# Safety_2019_V_3_0_Enable.net
KiCad netlist of a schematic drawn in Altium Designer
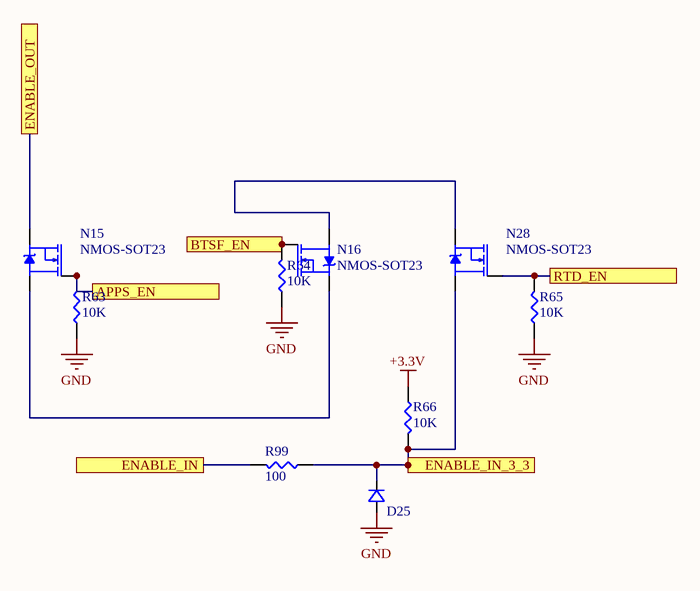
[diagram p0: Safety_2019_V_3_0_Enable.SchDoc]

(export (version "E")
  (design (tool "Eeschema 10.0.6"))
  (components
    (comp (ref "D25")
      (value "12V ZENER")
      (footprint "SOD123")
      (libsource (lib "ife19_Elec_Library") (part "DIODE-SOD123"))
    )
    (comp (ref "N15")
      (value "NMOS-SOT23")
      (footprint "SOT23")
      (libsource (lib "ife19_Elec_Library") (part "NMOS-SOT23"))
    )
    (comp (ref "N16")
      (value "NMOS-SOT23")
      (footprint "SOT23")
      (libsource (lib "ife19_Elec_Library") (part "NMOS-SOT23"))
    )
    (comp (ref "N28")
      (value "NMOS-SOT23")
      (footprint "SOT23")
      (libsource (lib "ife19_Elec_Library") (part "NMOS-SOT23"))
    )
    (comp (ref "R63")
      (value "10K")
      (footprint "RES-0603")
      (libsource (lib "ife19_Elec_Library") (part "RES-0603"))
    )
    (comp (ref "R64")
      (value "10K")
      (footprint "RES-0603")
      (libsource (lib "ife19_Elec_Library") (part "RES-0603"))
    )
    (comp (ref "R65")
      (value "10K")
      (footprint "RES-0603")
      (libsource (lib "ife19_Elec_Library") (part "RES-0603"))
    )
    (comp (ref "R66")
      (value "10K")
      (footprint "RES-0603")
      (libsource (lib "ife19_Elec_Library") (part "RES-0603"))
    )
    (comp (ref "R99")
      (value "100")
      (footprint "RES-0603")
      (libsource (lib "ife19_Elec_Library") (part "RES-0603"))
    )
  )
  (nets
    (net (code "1") (name "+3.3V") (class "Default")
      (node (ref "R66") (pin "1") (pinfunction "1_1") (pintype "passive"))
    )
    (net (code "2") (name "/APPS_EN") (class "Default")
      (node (ref "N15") (pin "1") (pinfunction "G_1") (pintype "passive"))
      (node (ref "R63") (pin "2") (pinfunction "2_2") (pintype "passive"))
    )
    (net (code "3") (name "/BTSF_EN") (class "Default")
      (node (ref "N16") (pin "1") (pinfunction "G_1") (pintype "passive"))
      (node (ref "R64") (pin "2") (pinfunction "2_2") (pintype "passive"))
    )
    (net (code "4") (name "/ENABLE_IN") (class "Default")
      (node (ref "R99") (pin "2") (pinfunction "2_2") (pintype "passive"))
    )
    (net (code "5") (name "/ENABLE_IN_3_3") (class "Default")
      (node (ref "D25") (pin "K") (pinfunction "K_K") (pintype "passive"))
      (node (ref "N28") (pin "2") (pinfunction "S_2") (pintype "passive"))
      (node (ref "R66") (pin "2") (pinfunction "2_2") (pintype "passive"))
      (node (ref "R99") (pin "1") (pinfunction "1_1") (pintype "passive"))
    )
    (net (code "6") (name "/ENABLE_OUT") (class "Default")
      (node (ref "N15") (pin "3") (pinfunction "D_3") (pintype "passive"))
    )
    (net (code "7") (name "/RTD_EN") (class "Default")
      (node (ref "N28") (pin "1") (pinfunction "G_1") (pintype "passive"))
      (node (ref "R65") (pin "2") (pinfunction "2_2") (pintype "passive"))
    )
    (net (code "8") (name "GND") (class "Default")
      (node (ref "D25") (pin "A") (pinfunction "A_A") (pintype "passive"))
      (node (ref "R63") (pin "1") (pinfunction "1_1") (pintype "passive"))
      (node (ref "R64") (pin "1") (pinfunction "1_1") (pintype "passive"))
      (node (ref "R65") (pin "1") (pinfunction "1_1") (pintype "passive"))
    )
    (net (code "9") (name "Net-(N15-S)") (class "Default")
      (node (ref "N15") (pin "2") (pinfunction "S_2") (pintype "passive"))
      (node (ref "N16") (pin "3") (pinfunction "D_3") (pintype "passive"))
    )
    (net (code "10") (name "Net-(N16-S)") (class "Default")
      (node (ref "N16") (pin "2") (pinfunction "S_2") (pintype "passive"))
      (node (ref "N28") (pin "3") (pinfunction "D_3") (pintype "passive"))
    )
  )
)
